# UART1.net
KiCad netlist of a schematic drawn in Altium Designer
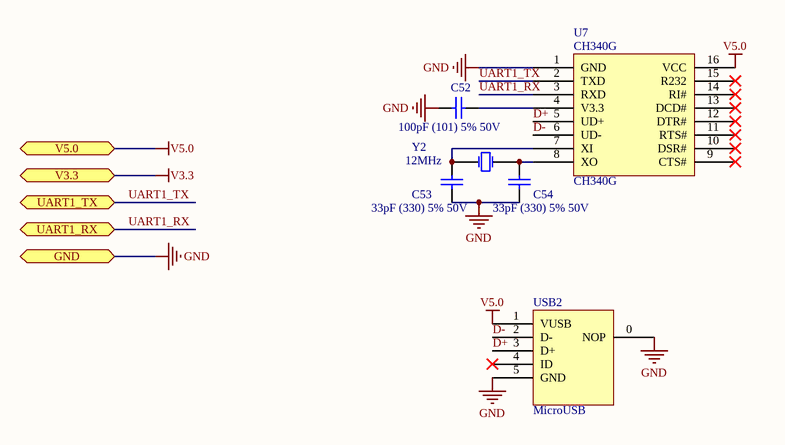
[diagram p0: UART1.SchDoc]

(export (version "E")
  (design (tool "Eeschema 10.0.6"))
  (components
    (comp (ref "C52")
      (value "100pF (101) 5% 50V")
      (footprint "0805_C")
      (description "贴片电容")
      (libsource (lib "Miscellaneous Devices LC") (part "0805 100pF (101) 5% 50V"))
    )
    (comp (ref "C53")
      (value "33pF (330) 5% 50V")
      (footprint "0805_C")
      (description "贴片电容")
      (libsource (lib "Miscellaneous Devices LC") (part "0805 33pF (330) 5% 50V"))
    )
    (comp (ref "C54")
      (value "33pF (330) 5% 50V")
      (footprint "0805_C")
      (description "贴片电容")
      (libsource (lib "Miscellaneous Devices LC") (part "0805 33pF (330) 5% 50V"))
    )
    (comp (ref "U7")
      (value "CH340G")
      (footprint "SOIC-16_150mil")
      (description "USB")
      (libsource (lib "Miscellaneous Devices LC") (part "CH340G_[C14267]"))
    )
    (comp (ref "USB2") (value "MicroUSB") (footprint "MicroUSB") (libsource (lib "mylib") (part "MicroUSB")))
    (comp (ref "Y2")
      (value "12MHz")
      (footprint "Y")
      (description "贴片晶振")
      (libsource (lib "Miscellaneous Devices LC") (part "SMD-5032_2P 8MHz 20ppm 20pF"))
    )
  )
  (nets
    (net (code "1") (name "/D+") (class "Default")
      (node (ref "U7") (pin "5") (pinfunction "UD+_5") (pintype "passive"))
      (node (ref "USB2") (pin "3") (pinfunction "D+_3") (pintype "passive"))
    )
    (net (code "2") (name "/D-") (class "Default")
      (node (ref "U7") (pin "6") (pinfunction "UD-_6") (pintype "passive"))
      (node (ref "USB2") (pin "2") (pinfunction "D-_2") (pintype "passive"))
    )
    (net (code "3") (name "/UART1_RX") (class "Default")
      (node (ref "U7") (pin "3") (pinfunction "RXD_3") (pintype "passive"))
    )
    (net (code "4") (name "/UART1_TX") (class "Default")
      (node (ref "U7") (pin "2") (pinfunction "TXD_2") (pintype "passive"))
    )
    (net (code "5") (name "GND") (class "Default")
      (node (ref "C52") (pin "1") (pinfunction "1_1") (pintype "passive"))
      (node (ref "C53") (pin "2") (pinfunction "2_2") (pintype "passive"))
      (node (ref "C54") (pin "2") (pinfunction "2_2") (pintype "passive"))
      (node (ref "U7") (pin "1") (pinfunction "GND_1") (pintype "passive"))
      (node (ref "USB2") (pin "0") (pinfunction "NOP_0") (pintype "passive"))
      (node (ref "USB2") (pin "5") (pinfunction "GND_5") (pintype "passive"))
    )
    (net (code "6") (name "Net-(U7-V3.3)") (class "Default")
      (node (ref "C52") (pin "2") (pinfunction "2_2") (pintype "passive"))
      (node (ref "U7") (pin "4") (pinfunction "V3.3_4") (pintype "passive"))
    )
    (net (code "7") (name "Net-(U7-XI)") (class "Default")
      (node (ref "C53") (pin "1") (pinfunction "1_1") (pintype "passive"))
      (node (ref "U7") (pin "7") (pinfunction "XI_7") (pintype "passive"))
      (node (ref "Y2") (pin "1") (pinfunction "OSC1_1") (pintype "passive"))
    )
    (net (code "8") (name "Net-(U7-XO)") (class "Default")
      (node (ref "C54") (pin "1") (pinfunction "1_1") (pintype "passive"))
      (node (ref "U7") (pin "8") (pinfunction "XO_8") (pintype "passive"))
      (node (ref "Y2") (pin "2") (pinfunction "OSC2_2") (pintype "passive"))
    )
    (net (code "10") (name "V5.0") (class "Default")
      (node (ref "U7") (pin "16") (pinfunction "VCC_16") (pintype "passive"))
      (node (ref "USB2") (pin "1") (pinfunction "VUSB_1") (pintype "passive"))
    )
    (net (code "11") (name "unconnected-(U7-CTS#-Pad9)") (class "Default")
      (node (ref "U7") (pin "9") (pinfunction "CTS#_9") (pintype "passive+no_connect"))
    )
    (net (code "12") (name "unconnected-(U7-DCD#-Pad13)") (class "Default")
      (node (ref "U7") (pin "13") (pinfunction "DCD#_13") (pintype "passive+no_connect"))
    )
    (net (code "13") (name "unconnected-(U7-DSR#-Pad10)") (class "Default")
      (node (ref "U7") (pin "10") (pinfunction "DSR#_10") (pintype "passive+no_connect"))
    )
    (net (code "14") (name "unconnected-(U7-DTR#-Pad12)") (class "Default")
      (node (ref "U7") (pin "12") (pinfunction "DTR#_12") (pintype "passive+no_connect"))
    )
    (net (code "15") (name "unconnected-(U7-R232-Pad15)") (class "Default")
      (node (ref "U7") (pin "15") (pinfunction "R232_15") (pintype "passive+no_connect"))
    )
    (net (code "16") (name "unconnected-(U7-RI#-Pad14)") (class "Default")
      (node (ref "U7") (pin "14") (pinfunction "RI#_14") (pintype "passive+no_connect"))
    )
    (net (code "17") (name "unconnected-(U7-RTS#-Pad11)") (class "Default")
      (node (ref "U7") (pin "11") (pinfunction "RTS#_11") (pintype "passive+no_connect"))
    )
    (net (code "18") (name "unconnected-(USB2-ID-Pad4)") (class "Default")
      (node (ref "USB2") (pin "4") (pinfunction "ID_4") (pintype "passive+no_connect"))
    )
  )
)
